# InterfacesB_NONISO422b.net
KiCad netlist of a schematic drawn in Altium Designer
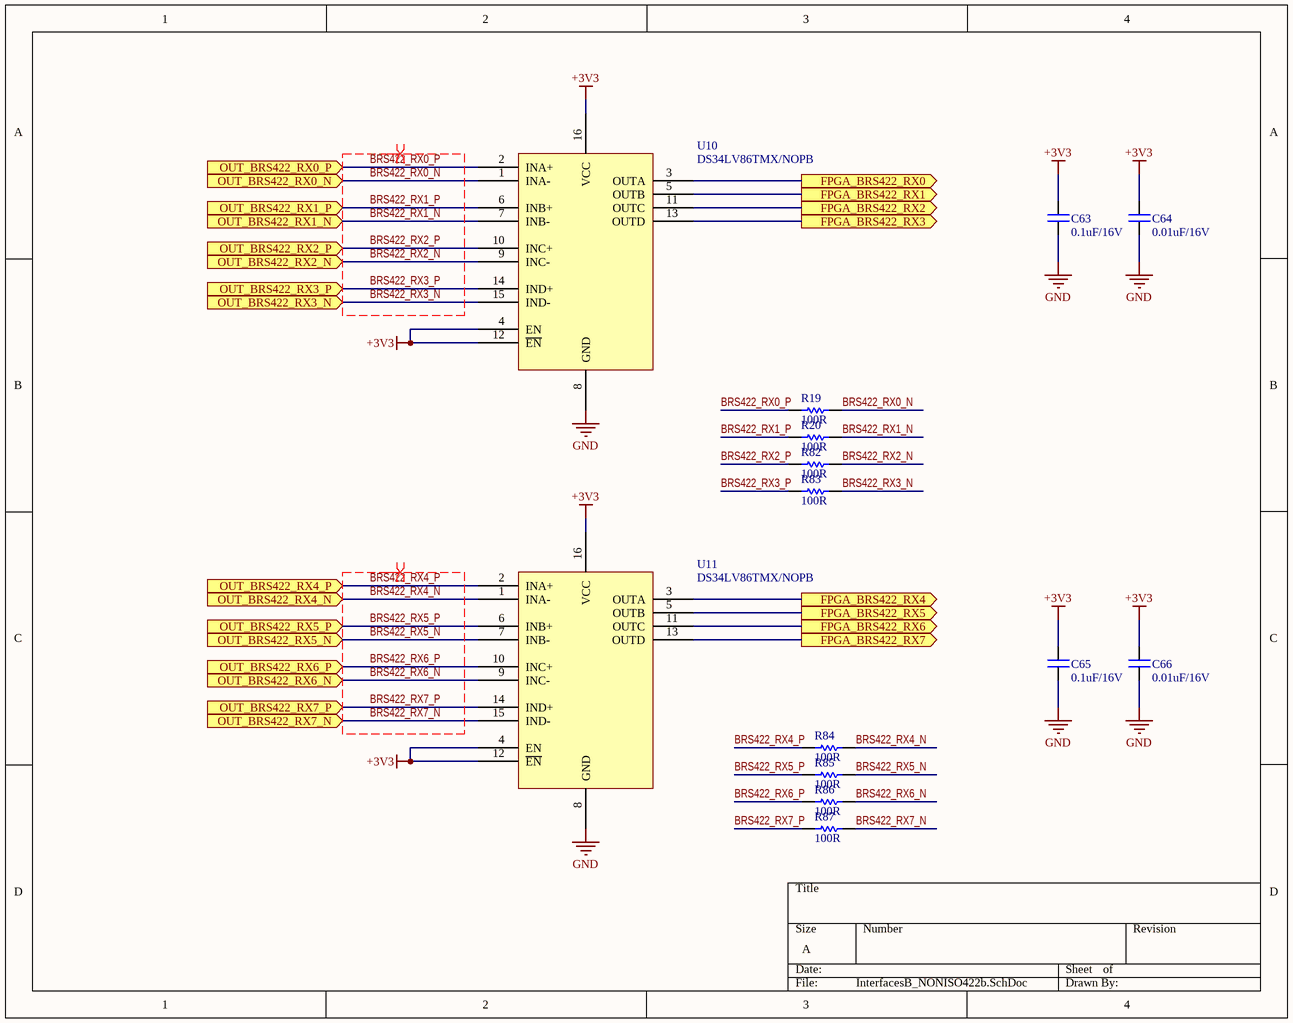
[diagram p0: InterfacesB_NONISO422b.SchDoc]

(export (version "E")
  (design (tool "Eeschema 10.0.6"))
  (components
    (comp (ref "C63")
      (value "0.1uF/16V")
      (footprint "CAP_0805")
      (fields (field (name "Comment") "CAP_0805"))
      (libsource (lib "AdapterLib") (part "CAP_0805"))
    )
    (comp (ref "C64")
      (value "0.01uF/16V")
      (footprint "CAP_0805")
      (fields (field (name "Comment") "CAP_0805"))
      (libsource (lib "AdapterLib") (part "CAP_0805"))
    )
    (comp (ref "C65")
      (value "0.1uF/16V")
      (footprint "CAP_0805")
      (fields (field (name "Comment") "CAP_0805"))
      (libsource (lib "AdapterLib") (part "CAP_0805"))
    )
    (comp (ref "C66")
      (value "0.01uF/16V")
      (footprint "CAP_0805")
      (fields (field (name "Comment") "CAP_0805"))
      (libsource (lib "AdapterLib") (part "CAP_0805"))
    )
    (comp (ref "R19")
      (value "100R")
      (footprint "RES_0805")
      (fields (field (name "Comment") "RES_0805"))
      (libsource (lib "AdapterLib") (part "RES_0805"))
    )
    (comp (ref "R20")
      (value "100R")
      (footprint "RES_0805")
      (fields (field (name "Comment") "RES_0805"))
      (libsource (lib "AdapterLib") (part "RES_0805"))
    )
    (comp (ref "R82")
      (value "100R")
      (footprint "RES_0805")
      (fields (field (name "Comment") "RES_0805"))
      (libsource (lib "AdapterLib") (part "RES_0805"))
    )
    (comp (ref "R83")
      (value "100R")
      (footprint "RES_0805")
      (fields (field (name "Comment") "RES_0805"))
      (libsource (lib "AdapterLib") (part "RES_0805"))
    )
    (comp (ref "R84")
      (value "100R")
      (footprint "RES_0805")
      (fields (field (name "Comment") "RES_0805"))
      (libsource (lib "AdapterLib") (part "RES_0805"))
    )
    (comp (ref "R85")
      (value "100R")
      (footprint "RES_0805")
      (fields (field (name "Comment") "RES_0805"))
      (libsource (lib "AdapterLib") (part "RES_0805"))
    )
    (comp (ref "R86")
      (value "100R")
      (footprint "RES_0805")
      (fields (field (name "Comment") "RES_0805"))
      (libsource (lib "AdapterLib") (part "RES_0805"))
    )
    (comp (ref "R87")
      (value "100R")
      (footprint "RES_0805")
      (fields (field (name "Comment") "RES_0805"))
      (libsource (lib "AdapterLib") (part "RES_0805"))
    )
    (comp (ref "U10")
      (value "DS34LV86TMX/NOPB")
      (footprint "DS34LV86TMX/NOPB")
      (libsource (lib "AdapterLib") (part "DS34LV86TMX/NOPB"))
    )
    (comp (ref "U11")
      (value "DS34LV86TMX/NOPB")
      (footprint "DS34LV86TMX/NOPB")
      (libsource (lib "AdapterLib") (part "DS34LV86TMX/NOPB"))
    )
  )
  (nets
    (net (code "1") (name "+3V3") (class "Default")
      (node (ref "C63") (pin "1") (pinfunction "1_1") (pintype "passive"))
      (node (ref "C64") (pin "1") (pinfunction "1_1") (pintype "passive"))
      (node (ref "C65") (pin "1") (pinfunction "1_1") (pintype "passive"))
      (node (ref "C66") (pin "1") (pinfunction "1_1") (pintype "passive"))
      (node (ref "U10") (pin "12") (pinfunction "~{EN}_12") (pintype "passive"))
      (node (ref "U10") (pin "16") (pinfunction "VCC_16") (pintype "passive"))
      (node (ref "U10") (pin "4") (pinfunction "EN_4") (pintype "passive"))
      (node (ref "U11") (pin "12") (pinfunction "~{EN}_12") (pintype "passive"))
      (node (ref "U11") (pin "16") (pinfunction "VCC_16") (pintype "passive"))
      (node (ref "U11") (pin "4") (pinfunction "EN_4") (pintype "passive"))
    )
    (net (code "2") (name "/BRS422_RX0_N") (class "Default")
      (node (ref "R19") (pin "1") (pinfunction "1_1") (pintype "passive"))
      (node (ref "U10") (pin "1") (pinfunction "INA-_1") (pintype "passive"))
    )
    (net (code "3") (name "/BRS422_RX0_P") (class "Default")
      (node (ref "R19") (pin "2") (pinfunction "2_2") (pintype "passive"))
      (node (ref "U10") (pin "2") (pinfunction "INA+_2") (pintype "passive"))
    )
    (net (code "4") (name "/BRS422_RX1_N") (class "Default")
      (node (ref "R20") (pin "1") (pinfunction "1_1") (pintype "passive"))
      (node (ref "U10") (pin "7") (pinfunction "INB-_7") (pintype "passive"))
    )
    (net (code "5") (name "/BRS422_RX1_P") (class "Default")
      (node (ref "R20") (pin "2") (pinfunction "2_2") (pintype "passive"))
      (node (ref "U10") (pin "6") (pinfunction "INB+_6") (pintype "passive"))
    )
    (net (code "6") (name "/BRS422_RX2_N") (class "Default")
      (node (ref "R82") (pin "1") (pinfunction "1_1") (pintype "passive"))
      (node (ref "U10") (pin "9") (pinfunction "INC-_9") (pintype "passive"))
    )
    (net (code "7") (name "/BRS422_RX2_P") (class "Default")
      (node (ref "R82") (pin "2") (pinfunction "2_2") (pintype "passive"))
      (node (ref "U10") (pin "10") (pinfunction "INC+_10") (pintype "passive"))
    )
    (net (code "8") (name "/BRS422_RX3_N") (class "Default")
      (node (ref "R83") (pin "1") (pinfunction "1_1") (pintype "passive"))
      (node (ref "U10") (pin "15") (pinfunction "IND-_15") (pintype "passive"))
    )
    (net (code "9") (name "/BRS422_RX3_P") (class "Default")
      (node (ref "R83") (pin "2") (pinfunction "2_2") (pintype "passive"))
      (node (ref "U10") (pin "14") (pinfunction "IND+_14") (pintype "passive"))
    )
    (net (code "10") (name "/BRS422_RX4_N") (class "Default")
      (node (ref "R84") (pin "1") (pinfunction "1_1") (pintype "passive"))
      (node (ref "U11") (pin "1") (pinfunction "INA-_1") (pintype "passive"))
    )
    (net (code "11") (name "/BRS422_RX4_P") (class "Default")
      (node (ref "R84") (pin "2") (pinfunction "2_2") (pintype "passive"))
      (node (ref "U11") (pin "2") (pinfunction "INA+_2") (pintype "passive"))
    )
    (net (code "12") (name "/BRS422_RX5_N") (class "Default")
      (node (ref "R85") (pin "1") (pinfunction "1_1") (pintype "passive"))
      (node (ref "U11") (pin "7") (pinfunction "INB-_7") (pintype "passive"))
    )
    (net (code "13") (name "/BRS422_RX5_P") (class "Default")
      (node (ref "R85") (pin "2") (pinfunction "2_2") (pintype "passive"))
      (node (ref "U11") (pin "6") (pinfunction "INB+_6") (pintype "passive"))
    )
    (net (code "14") (name "/BRS422_RX6_N") (class "Default")
      (node (ref "R86") (pin "1") (pinfunction "1_1") (pintype "passive"))
      (node (ref "U11") (pin "9") (pinfunction "INC-_9") (pintype "passive"))
    )
    (net (code "15") (name "/BRS422_RX6_P") (class "Default")
      (node (ref "R86") (pin "2") (pinfunction "2_2") (pintype "passive"))
      (node (ref "U11") (pin "10") (pinfunction "INC+_10") (pintype "passive"))
    )
    (net (code "16") (name "/BRS422_RX7_N") (class "Default")
      (node (ref "R87") (pin "1") (pinfunction "1_1") (pintype "passive"))
      (node (ref "U11") (pin "15") (pinfunction "IND-_15") (pintype "passive"))
    )
    (net (code "17") (name "/BRS422_RX7_P") (class "Default")
      (node (ref "R87") (pin "2") (pinfunction "2_2") (pintype "passive"))
      (node (ref "U11") (pin "14") (pinfunction "IND+_14") (pintype "passive"))
    )
    (net (code "18") (name "/FPGA_BRS422_RX0") (class "Default")
      (node (ref "U10") (pin "3") (pinfunction "OUTA_3") (pintype "passive"))
    )
    (net (code "19") (name "/FPGA_BRS422_RX1") (class "Default")
      (node (ref "U10") (pin "5") (pinfunction "OUTB_5") (pintype "passive"))
    )
    (net (code "20") (name "/FPGA_BRS422_RX2") (class "Default")
      (node (ref "U10") (pin "11") (pinfunction "OUTC_11") (pintype "passive"))
    )
    (net (code "21") (name "/FPGA_BRS422_RX3") (class "Default")
      (node (ref "U10") (pin "13") (pinfunction "OUTD_13") (pintype "passive"))
    )
    (net (code "22") (name "/FPGA_BRS422_RX4") (class "Default")
      (node (ref "U11") (pin "3") (pinfunction "OUTA_3") (pintype "passive"))
    )
    (net (code "23") (name "/FPGA_BRS422_RX5") (class "Default")
      (node (ref "U11") (pin "5") (pinfunction "OUTB_5") (pintype "passive"))
    )
    (net (code "24") (name "/FPGA_BRS422_RX6") (class "Default")
      (node (ref "U11") (pin "11") (pinfunction "OUTC_11") (pintype "passive"))
    )
    (net (code "25") (name "/FPGA_BRS422_RX7") (class "Default")
      (node (ref "U11") (pin "13") (pinfunction "OUTD_13") (pintype "passive"))
    )
    (net (code "26") (name "GND") (class "Default")
      (node (ref "C63") (pin "2") (pinfunction "2_2") (pintype "passive"))
      (node (ref "C64") (pin "2") (pinfunction "2_2") (pintype "passive"))
      (node (ref "C65") (pin "2") (pinfunction "2_2") (pintype "passive"))
      (node (ref "C66") (pin "2") (pinfunction "2_2") (pintype "passive"))
      (node (ref "U10") (pin "8") (pinfunction "GND_8") (pintype "passive"))
      (node (ref "U11") (pin "8") (pinfunction "GND_8") (pintype "passive"))
    )
  )
)
